# Counter.net
KiCad netlist of a schematic drawn in Altium Designer
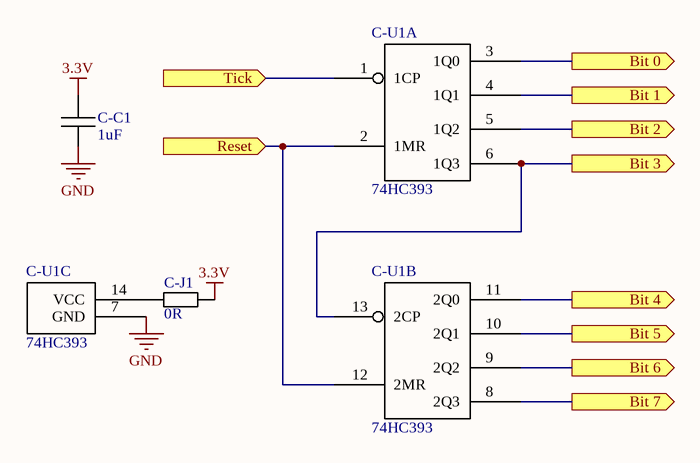
[diagram p0: Counter.SchDoc]

(export (version "E")
  (design (tool "Eeschema 10.0.6"))
  (components
    (comp (ref "C-C1")
      (value "1uF")
      (footprint "C 0805 / 2012")
      (libsource (lib "Standard") (part "Capacitor"))
    )
    (comp (ref "C-J1")
      (value "0R")
      (footprint "R 0805 / 2012 wide")
      (libsource (lib "Standard") (part "Resistor"))
    )
    (comp (ref "C-U1")
      (value "74HC393")
      (footprint "SOIC-14")
      (description "Dual 4-Bit Counter")
      (libsource (lib "ICs") (part "74HC393"))
    )
  )
  (nets
    (net (code "1") (name "/Bit 0") (class "Default")
      (node (ref "C-U1") (pin "3") (pinfunction "1Q0_3") (pintype "passive"))
    )
    (net (code "2") (name "/Bit 1") (class "Default")
      (node (ref "C-U1") (pin "4") (pinfunction "1Q1_4") (pintype "passive"))
    )
    (net (code "3") (name "/Bit 2") (class "Default")
      (node (ref "C-U1") (pin "5") (pinfunction "1Q2_5") (pintype "passive"))
    )
    (net (code "4") (name "/Bit 3") (class "Default")
      (node (ref "C-U1") (pin "13") (pinfunction "2CP_13") (pintype "passive"))
      (node (ref "C-U1") (pin "6") (pinfunction "1Q3_6") (pintype "passive"))
    )
    (net (code "5") (name "/Bit 4") (class "Default")
      (node (ref "C-U1") (pin "11") (pinfunction "2Q0_11") (pintype "passive"))
    )
    (net (code "6") (name "/Bit 5") (class "Default")
      (node (ref "C-U1") (pin "10") (pinfunction "2Q1_10") (pintype "passive"))
    )
    (net (code "7") (name "/Bit 6") (class "Default")
      (node (ref "C-U1") (pin "9") (pinfunction "2Q2_9") (pintype "passive"))
    )
    (net (code "8") (name "/Bit 7") (class "Default")
      (node (ref "C-U1") (pin "8") (pinfunction "2Q3_8") (pintype "passive"))
    )
    (net (code "9") (name "/Reset") (class "Default")
      (node (ref "C-U1") (pin "12") (pinfunction "2MR_12") (pintype "passive"))
      (node (ref "C-U1") (pin "2") (pinfunction "1MR_2") (pintype "passive"))
    )
    (net (code "10") (name "/Tick") (class "Default")
      (node (ref "C-U1") (pin "1") (pinfunction "1CP_1") (pintype "passive"))
    )
    (net (code "11") (name "3.3V") (class "Default")
      (node (ref "C-C1") (pin "1") (pinfunction "1_1") (pintype "passive"))
      (node (ref "C-J1") (pin "2") (pinfunction "2_2") (pintype "passive"))
    )
    (net (code "12") (name "GND") (class "Default")
      (node (ref "C-C1") (pin "2") (pinfunction "1_2") (pintype "passive"))
      (node (ref "C-U1") (pin "7") (pinfunction "GND_7") (pintype "passive"))
    )
    (net (code "13") (name "Net-(C-U1C-VCC)") (class "Default")
      (node (ref "C-J1") (pin "1") (pinfunction "1_1") (pintype "passive"))
      (node (ref "C-U1") (pin "14") (pinfunction "VCC_14") (pintype "passive"))
    )
  )
)
